# v1_0.net
KiCad netlist of a schematic drawn in Altium Designer
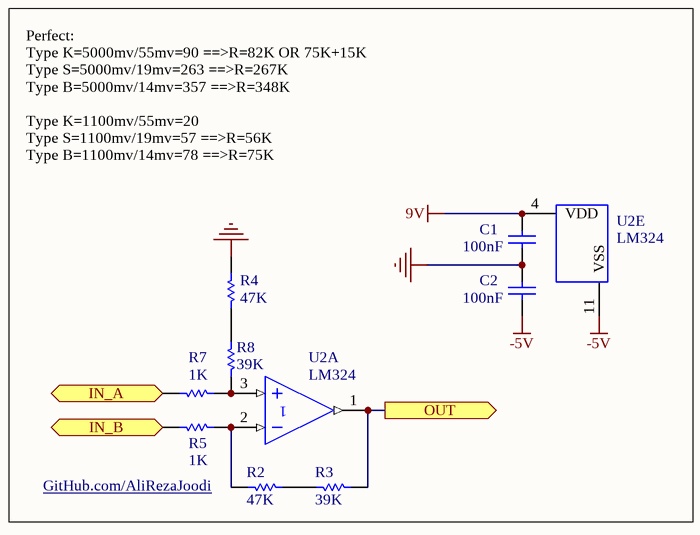
[diagram p0: v1.0.SchDoc]

(export (version "E")
  (design (tool "Eeschema 10.0.6"))
  (components
    (comp (ref "C1")
      (value "100nF")
      (footprint "CAPNTO2.54-3.05x1.78A")
      (description "Capacitor")
      (fields (field (name "MANUFACTURER") "Generic Components") (field (name "PUBLISHER") "Altium Limited"))
      (libsource (lib "Miscellaneous Devices") (part "Cap"))
    )
    (comp (ref "C2")
      (value "100nF")
      (footprint "CAPNTO2.54-3.05x1.78A")
      (description "Capacitor")
      (fields (field (name "MANUFACTURER") "Generic Components") (field (name "PUBLISHER") "Altium Limited"))
      (libsource (lib "Miscellaneous Devices") (part "Cap"))
    )
    (comp (ref "R2")
      (value "47K")
      (footprint "AXIAL-0.4")
      (description "Resistor")
      (fields (field (name "PUBLISHER") "Altium Limited"))
      (libsource (lib "Miscellaneous Devices") (part "Res1"))
    )
    (comp (ref "R3")
      (value "39K")
      (footprint "AXIAL-0.4")
      (description "Resistor")
      (fields (field (name "PUBLISHER") "Altium Limited"))
      (libsource (lib "Miscellaneous Devices") (part "Res1"))
    )
    (comp (ref "R4")
      (value "47K")
      (footprint "AXIAL-0.4")
      (description "Resistor")
      (fields (field (name "PUBLISHER") "Altium Limited"))
      (libsource (lib "Miscellaneous Devices") (part "Res1"))
    )
    (comp (ref "R5")
      (value "1K")
      (footprint "AXIAL-0.4")
      (description "Resistor")
      (fields (field (name "PUBLISHER") "Altium Limited"))
      (libsource (lib "Miscellaneous Devices") (part "Res1"))
    )
    (comp (ref "R7")
      (value "1K")
      (footprint "AXIAL-0.4")
      (description "Resistor")
      (fields (field (name "PUBLISHER") "Altium Limited"))
      (libsource (lib "Miscellaneous Devices") (part "Res1"))
    )
    (comp (ref "R8")
      (value "39K")
      (footprint "AXIAL-0.4")
      (description "Resistor")
      (fields (field (name "PUBLISHER") "Altium Limited"))
      (libsource (lib "Miscellaneous Devices") (part "Res1"))
    )
    (comp (ref "U2")
      (value "LM324")
      (footprint "646-06")
      (description "Quad Low-Power Operational Amplifier")
      (fields (field (name "PUBLISHER") "Altium Limited"))
      (libsource (lib "my Libraries") (part "LM324"))
    )
  )
  (nets
    (net (code "1") (name "-5V") (class "Default")
      (node (ref "C2") (pin "2") (pinfunction "2_2") (pintype "passive"))
      (node (ref "U2") (pin "11") (pinfunction "VSS_11") (pintype "power_in"))
    )
    (net (code "2") (name "/IN_A") (class "Default")
      (node (ref "R7") (pin "2") (pinfunction "2_2") (pintype "passive"))
    )
    (net (code "3") (name "/IN_B") (class "Default")
      (node (ref "R5") (pin "2") (pinfunction "2_2") (pintype "passive"))
    )
    (net (code "4") (name "/OUT") (class "Default")
      (node (ref "R3") (pin "2") (pinfunction "2_2") (pintype "passive"))
      (node (ref "U2") (pin "1") (pinfunction "OUT_1") (pintype "output"))
    )
    (net (code "5") (name "9V") (class "Default")
      (node (ref "C1") (pin "1") (pinfunction "1_1") (pintype "passive"))
      (node (ref "U2") (pin "4") (pinfunction "VDD_4") (pintype "passive"))
    )
    (net (code "6") (name "GND") (class "Default")
      (node (ref "C1") (pin "2") (pinfunction "2_2") (pintype "passive"))
      (node (ref "C2") (pin "1") (pinfunction "1_1") (pintype "passive"))
      (node (ref "R4") (pin "2") (pinfunction "2_2") (pintype "passive"))
    )
    (net (code "7") (name "Net-(R2-Pad2)") (class "Default")
      (node (ref "R2") (pin "2") (pinfunction "2_2") (pintype "passive"))
      (node (ref "R3") (pin "1") (pinfunction "1_1") (pintype "passive"))
    )
    (net (code "8") (name "Net-(R4-Pad1)") (class "Default")
      (node (ref "R4") (pin "1") (pinfunction "1_1") (pintype "passive"))
      (node (ref "R8") (pin "2") (pinfunction "2_2") (pintype "passive"))
    )
    (net (code "9") (name "Net-(U2A-IN+)") (class "Default")
      (node (ref "R7") (pin "1") (pinfunction "1_1") (pintype "passive"))
      (node (ref "R8") (pin "1") (pinfunction "1_1") (pintype "passive"))
      (node (ref "U2") (pin "3") (pinfunction "IN+_3") (pintype "input"))
    )
    (net (code "10") (name "Net-(U2A-IN-)") (class "Default")
      (node (ref "R2") (pin "1") (pinfunction "1_1") (pintype "passive"))
      (node (ref "R5") (pin "1") (pinfunction "1_1") (pintype "passive"))
      (node (ref "U2") (pin "2") (pinfunction "IN-_2") (pintype "input"))
    )
  )
)
